# design.net
KiCad netlist of a schematic drawn in Altium Designer
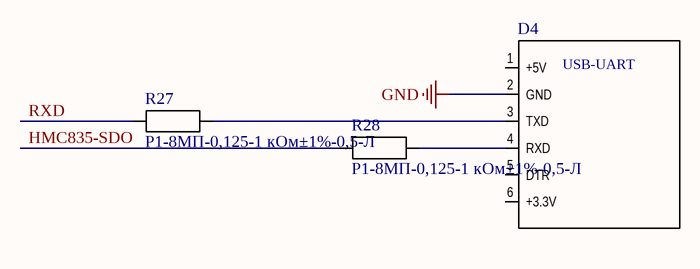
[diagram p0: Последовательный порт.SchDoc]

(export (version "E")
  (design (tool "Eeschema 10.0.6"))
  (components
    (comp (ref "D4")
      (value "~")
      (footprint "USB-UART-CP2102")
      (fields (field (name "MANUFACTURER") "China") (field (name "MANUFACTURERPARTNUMBER") "CJMUC CP2102"))
      (libsource (lib "МИКРОСХЕМЫ") (part "USB-UART"))
    )
    (comp (ref "R27")
      (value "Р1-8МП-0,125-1 кОм±1%-0,5-Л")
      (footprint "Р1-8МП-0,125")
      (fields (field (name "TOLERANCE") "±1%-0,5-Л") (field (name "PARTNUMBER") "ОЖ0.467.164ТУ"))
      (libsource (lib "РЕЗИСТОРЫ") (part "Р1-8МП-0,125-1 кОм±1%"))
    )
    (comp (ref "R28")
      (value "Р1-8МП-0,125-1 кОм±1%-0,5-Л")
      (footprint "Р1-8МП-0,125")
      (fields (field (name "TOLERANCE") "±1%-0,5-Л") (field (name "PARTNUMBER") "ОЖ0.467.164ТУ"))
      (libsource (lib "РЕЗИСТОРЫ") (part "Р1-8МП-0,125-1 кОм±1%"))
    )
  )
  (nets
    (net (code "1") (name "/HMC835-SDO") (class "Default")
      (node (ref "R28") (pin "1") (pinfunction "1_1") (pintype "passive"))
    )
    (net (code "2") (name "/RXD") (class "Default")
      (node (ref "R27") (pin "1") (pinfunction "1_1") (pintype "passive"))
    )
    (net (code "3") (name "GND") (class "Default")
      (node (ref "D4") (pin "2") (pinfunction "GND_2") (pintype "passive"))
    )
    (net (code "4") (name "Net-(D4-RXD)") (class "Default")
      (node (ref "D4") (pin "4") (pinfunction "RXD_4") (pintype "passive"))
      (node (ref "R28") (pin "2") (pinfunction "2_2") (pintype "passive"))
    )
    (net (code "5") (name "Net-(D4-TXD)") (class "Default")
      (node (ref "D4") (pin "3") (pinfunction "TXD_3") (pintype "passive"))
      (node (ref "R27") (pin "2") (pinfunction "2_2") (pintype "passive"))
    )
    (net (code "6") (name "unconnected-(D4-+3.3V-Pad6)") (class "Default")
      (node (ref "D4") (pin "6") (pinfunction "+3.3V_6") (pintype "passive"))
    )
    (net (code "7") (name "unconnected-(D4-+5V-Pad1)") (class "Default")
      (node (ref "D4") (pin "1") (pinfunction "+5V_1") (pintype "passive"))
    )
    (net (code "8") (name "unconnected-(D4-DTR-Pad5)") (class "Default")
      (node (ref "D4") (pin "5") (pinfunction "DTR_5") (pintype "passive"))
    )
  )
)
